# adapter_v1_2.net
KiCad netlist of a schematic drawn in EAGLE
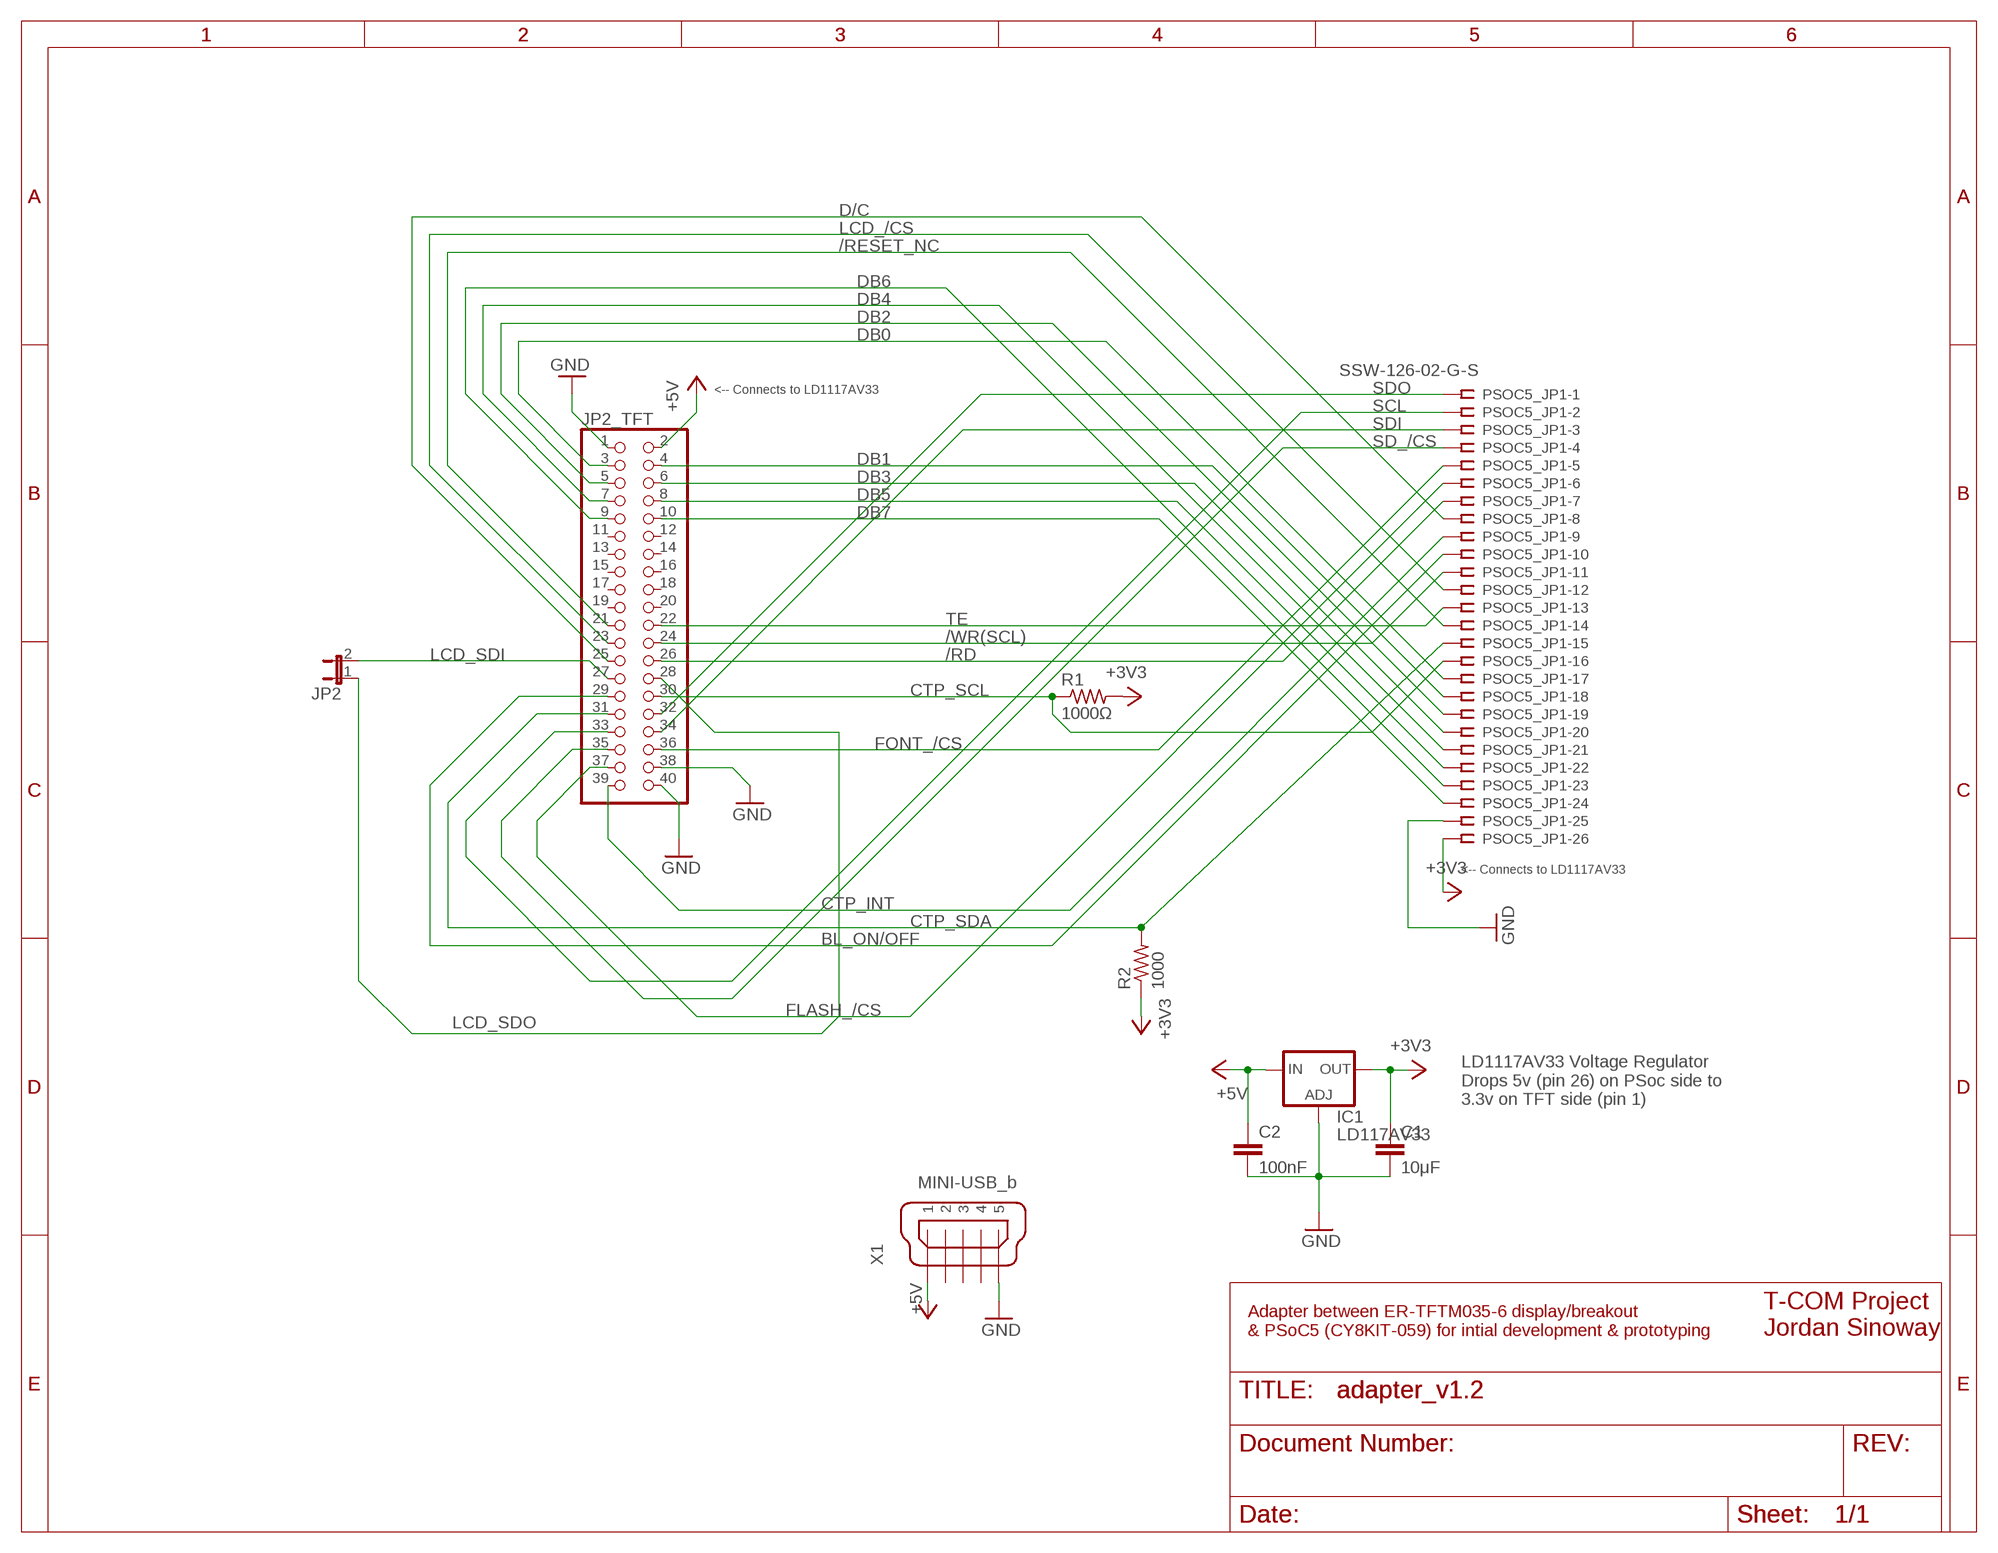
[diagram p0: schematic, sheet 1]

(export (version "E")
  (design (tool "Eeschema 10.0.6"))
  (components
    (comp (ref "C1")
      (value "10μF")
      (footprint "eagle-import:C2.5-2")
      (libsource (lib "eagle-import") (part "C2.5/2"))
    )
    (comp (ref "C2")
      (value "100nF")
      (footprint "eagle-import:C2.5-2")
      (libsource (lib "eagle-import") (part "C2.5/2"))
    )
    (comp (ref "IC1")
      (value "LD117AV33")
      (footprint "eagle-import:TO220L1")
      (libsource (lib "eagle-import") (part "LD117A?V33"))
    )
    (comp (ref "JP2")
      (value "JP1E")
      (footprint "eagle-import:JP1")
      (libsource (lib "eagle-import") (part "JP1E"))
    )
    (comp (ref "JP2_TFT")
      (value "PINHD-2X20")
      (footprint "eagle-import:2X20")
      (libsource (lib "eagle-import") (part "PINHD-2X20"))
    )
    (comp (ref "PSOC5_JP1")
      (value "SSW-126-02-G-S")
      (footprint "eagle-import:SSW-126-02-G-S")
      (fields (field (name "MF") "Samtec Inc."))
      (libsource (lib "eagle-import") (part "SSW-126-02-G-S"))
    )
    (comp (ref "R1")
      (value "1000Ω")
      (footprint "eagle-import:0204_7")
      (libsource (lib "eagle-import") (part "R-US_0204/7"))
    )
    (comp (ref "R2")
      (value "1000")
      (footprint "eagle-import:0204_7")
      (libsource (lib "eagle-import") (part "R-US_0204/7"))
    )
    (comp (ref "X1")
      (value "MINI-USB_b")
      (footprint "eagle-import:32005-601")
      (libsource (lib "eagle-import") (part "MINI-USB_SHIELD5P2-32005-601"))
    )
  )
  (nets
    (net (code "1") (name "+3V3") (class "Default")
      (node (ref "C1") (pin "1") (pinfunction "1_1") (pintype "passive"))
      (node (ref "IC1") (pin "2") (pinfunction "OUT_2") (pintype "passive"))
      (node (ref "PSOC5_JP1") (pin "26") (pinfunction "1_26") (pintype "passive"))
      (node (ref "R1") (pin "2") (pinfunction "2_2") (pintype "passive"))
      (node (ref "R2") (pin "1") (pinfunction "1_1") (pintype "passive"))
    )
    (net (code "2") (name "+5V") (class "Default")
      (node (ref "C2") (pin "1") (pinfunction "1_1") (pintype "passive"))
      (node (ref "IC1") (pin "3") (pinfunction "IN_3") (pintype "input"))
      (node (ref "JP2_TFT") (pin "2") (pinfunction "2_2") (pintype "passive"))
      (node (ref "X1") (pin "1") (pinfunction "1_1") (pintype "passive"))
    )
    (net (code "3") (name "/BL_ON{slash}OFF") (class "Default")
      (node (ref "JP2_TFT") (pin "29") (pinfunction "29_29") (pintype "passive"))
      (node (ref "PSOC5_JP1") (pin "10") (pinfunction "1_10") (pintype "passive"))
    )
    (net (code "4") (name "/CTP_INT") (class "Default")
      (node (ref "JP2_TFT") (pin "39") (pinfunction "39_39") (pintype "passive"))
      (node (ref "PSOC5_JP1") (pin "9") (pinfunction "1_9") (pintype "passive"))
    )
    (net (code "5") (name "/CTP_SCL") (class "Default")
      (node (ref "JP2_TFT") (pin "30") (pinfunction "30_30") (pintype "passive"))
      (node (ref "PSOC5_JP1") (pin "16") (pinfunction "1_16") (pintype "passive"))
      (node (ref "R1") (pin "1") (pinfunction "1_1") (pintype "passive"))
    )
    (net (code "6") (name "/CTP_SDA") (class "Default")
      (node (ref "JP2_TFT") (pin "31") (pinfunction "31_31") (pintype "passive"))
      (node (ref "PSOC5_JP1") (pin "15") (pinfunction "1_15") (pintype "passive"))
      (node (ref "R2") (pin "2") (pinfunction "2_2") (pintype "passive"))
    )
    (net (code "7") (name "/DB0") (class "Default")
      (node (ref "JP2_TFT") (pin "3") (pinfunction "3_3") (pintype "passive"))
      (node (ref "PSOC5_JP1") (pin "17") (pinfunction "1_17") (pintype "passive"))
    )
    (net (code "8") (name "/DB1") (class "Default")
      (node (ref "JP2_TFT") (pin "4") (pinfunction "4_4") (pintype "passive"))
      (node (ref "PSOC5_JP1") (pin "18") (pinfunction "1_18") (pintype "passive"))
    )
    (net (code "9") (name "/DB2") (class "Default")
      (node (ref "JP2_TFT") (pin "5") (pinfunction "5_5") (pintype "passive"))
      (node (ref "PSOC5_JP1") (pin "19") (pinfunction "1_19") (pintype "passive"))
    )
    (net (code "10") (name "/DB3") (class "Default")
      (node (ref "JP2_TFT") (pin "6") (pinfunction "6_6") (pintype "passive"))
      (node (ref "PSOC5_JP1") (pin "20") (pinfunction "1_20") (pintype "passive"))
    )
    (net (code "11") (name "/DB4") (class "Default")
      (node (ref "JP2_TFT") (pin "7") (pinfunction "7_7") (pintype "passive"))
      (node (ref "PSOC5_JP1") (pin "21") (pinfunction "1_21") (pintype "passive"))
    )
    (net (code "12") (name "/DB5") (class "Default")
      (node (ref "JP2_TFT") (pin "8") (pinfunction "8_8") (pintype "passive"))
      (node (ref "PSOC5_JP1") (pin "22") (pinfunction "1_22") (pintype "passive"))
    )
    (net (code "13") (name "/DB6") (class "Default")
      (node (ref "JP2_TFT") (pin "9") (pinfunction "9_9") (pintype "passive"))
      (node (ref "PSOC5_JP1") (pin "23") (pinfunction "1_23") (pintype "passive"))
    )
    (net (code "14") (name "/DB7") (class "Default")
      (node (ref "JP2_TFT") (pin "10") (pinfunction "10_10") (pintype "passive"))
      (node (ref "PSOC5_JP1") (pin "24") (pinfunction "1_24") (pintype "passive"))
    )
    (net (code "15") (name "/D{slash}C") (class "Default")
      (node (ref "JP2_TFT") (pin "25") (pinfunction "25_25") (pintype "passive"))
      (node (ref "PSOC5_JP1") (pin "8") (pinfunction "1_8") (pintype "passive"))
    )
    (net (code "16") (name "/FLASH_{slash}CS") (class "Default")
      (node (ref "JP2_TFT") (pin "37") (pinfunction "37_37") (pintype "passive"))
      (node (ref "PSOC5_JP1") (pin "6") (pinfunction "1_6") (pintype "passive"))
    )
    (net (code "17") (name "/FONT_{slash}CS") (class "Default")
      (node (ref "JP2_TFT") (pin "36") (pinfunction "36_36") (pintype "passive"))
      (node (ref "PSOC5_JP1") (pin "5") (pinfunction "1_5") (pintype "passive"))
    )
    (net (code "18") (name "/LCD_SDI") (class "Default")
      (node (ref "JP2") (pin "2") (pinfunction "2_2") (pintype "passive"))
      (node (ref "JP2_TFT") (pin "27") (pinfunction "27_27") (pintype "passive"))
    )
    (net (code "19") (name "/LCD_SDO") (class "Default")
      (node (ref "JP2") (pin "1") (pinfunction "1_1") (pintype "passive"))
      (node (ref "JP2_TFT") (pin "28") (pinfunction "28_28") (pintype "passive"))
    )
    (net (code "20") (name "/LCD_{slash}CS") (class "Default")
      (node (ref "JP2_TFT") (pin "23") (pinfunction "23_23") (pintype "passive"))
      (node (ref "PSOC5_JP1") (pin "12") (pinfunction "1_12") (pintype "passive"))
    )
    (net (code "21") (name "/SCL") (class "Default")
      (node (ref "JP2_TFT") (pin "33") (pinfunction "33_33") (pintype "passive"))
      (node (ref "PSOC5_JP1") (pin "2") (pinfunction "1_2") (pintype "passive"))
    )
    (net (code "22") (name "/SDI") (class "Default")
      (node (ref "JP2_TFT") (pin "34") (pinfunction "34_34") (pintype "passive"))
      (node (ref "PSOC5_JP1") (pin "3") (pinfunction "1_3") (pintype "passive"))
    )
    (net (code "23") (name "/SDO") (class "Default")
      (node (ref "JP2_TFT") (pin "32") (pinfunction "32_32") (pintype "passive"))
      (node (ref "PSOC5_JP1") (pin "1") (pinfunction "1_1") (pintype "passive"))
    )
    (net (code "24") (name "/SD_{slash}CS") (class "Default")
      (node (ref "JP2_TFT") (pin "35") (pinfunction "35_35") (pintype "passive"))
      (node (ref "PSOC5_JP1") (pin "4") (pinfunction "1_4") (pintype "passive"))
    )
    (net (code "25") (name "/TE") (class "Default")
      (node (ref "JP2_TFT") (pin "22") (pinfunction "22_22") (pintype "passive"))
      (node (ref "PSOC5_JP1") (pin "13") (pinfunction "1_13") (pintype "passive"))
    )
    (net (code "26") (name "/{slash}RD") (class "Default")
      (node (ref "JP2_TFT") (pin "26") (pinfunction "26_26") (pintype "passive"))
      (node (ref "PSOC5_JP1") (pin "7") (pinfunction "1_7") (pintype "passive"))
    )
    (net (code "27") (name "/{slash}RESET_NC") (class "Default")
      (node (ref "JP2_TFT") (pin "21") (pinfunction "21_21") (pintype "passive"))
      (node (ref "PSOC5_JP1") (pin "14") (pinfunction "1_14") (pintype "passive"))
    )
    (net (code "28") (name "/{slash}WR(SCL)") (class "Default")
      (node (ref "JP2_TFT") (pin "24") (pinfunction "24_24") (pintype "passive"))
      (node (ref "PSOC5_JP1") (pin "11") (pinfunction "1_11") (pintype "passive"))
    )
    (net (code "29") (name "GND") (class "Default")
      (node (ref "C1") (pin "2") (pinfunction "2_2") (pintype "passive"))
      (node (ref "C2") (pin "2") (pinfunction "2_2") (pintype "passive"))
      (node (ref "IC1") (pin "1") (pinfunction "ADJ_1") (pintype "input"))
      (node (ref "JP2_TFT") (pin "1") (pinfunction "1_1") (pintype "passive"))
      (node (ref "JP2_TFT") (pin "38") (pinfunction "38_38") (pintype "passive"))
      (node (ref "JP2_TFT") (pin "40") (pinfunction "40_40") (pintype "passive"))
      (node (ref "PSOC5_JP1") (pin "25") (pinfunction "1_25") (pintype "passive"))
      (node (ref "X1") (pin "5") (pinfunction "5_5") (pintype "passive"))
    )
    (net (code "30") (name "unconnected-(JP2_TFT-Pad11)") (class "Default")
      (node (ref "JP2_TFT") (pin "11") (pinfunction "11_11") (pintype "passive"))
    )
    (net (code "31") (name "unconnected-(JP2_TFT-Pad12)") (class "Default")
      (node (ref "JP2_TFT") (pin "12") (pinfunction "12_12") (pintype "passive"))
    )
    (net (code "32") (name "unconnected-(JP2_TFT-Pad13)") (class "Default")
      (node (ref "JP2_TFT") (pin "13") (pinfunction "13_13") (pintype "passive"))
    )
    (net (code "33") (name "unconnected-(JP2_TFT-Pad14)") (class "Default")
      (node (ref "JP2_TFT") (pin "14") (pinfunction "14_14") (pintype "passive"))
    )
    (net (code "34") (name "unconnected-(JP2_TFT-Pad15)") (class "Default")
      (node (ref "JP2_TFT") (pin "15") (pinfunction "15_15") (pintype "passive"))
    )
    (net (code "35") (name "unconnected-(JP2_TFT-Pad16)") (class "Default")
      (node (ref "JP2_TFT") (pin "16") (pinfunction "16_16") (pintype "passive"))
    )
    (net (code "36") (name "unconnected-(JP2_TFT-Pad17)") (class "Default")
      (node (ref "JP2_TFT") (pin "17") (pinfunction "17_17") (pintype "passive"))
    )
    (net (code "37") (name "unconnected-(JP2_TFT-Pad18)") (class "Default")
      (node (ref "JP2_TFT") (pin "18") (pinfunction "18_18") (pintype "passive"))
    )
    (net (code "38") (name "unconnected-(JP2_TFT-Pad19)") (class "Default")
      (node (ref "JP2_TFT") (pin "19") (pinfunction "19_19") (pintype "passive"))
    )
    (net (code "39") (name "unconnected-(JP2_TFT-Pad20)") (class "Default")
      (node (ref "JP2_TFT") (pin "20") (pinfunction "20_20") (pintype "passive"))
    )
    (net (code "40") (name "unconnected-(X1-Pad2)") (class "Default")
      (node (ref "X1") (pin "2") (pinfunction "2_2") (pintype "passive"))
    )
    (net (code "41") (name "unconnected-(X1-Pad3)") (class "Default")
      (node (ref "X1") (pin "3") (pinfunction "3_3") (pintype "passive"))
    )
    (net (code "42") (name "unconnected-(X1-Pad4)") (class "Default")
      (node (ref "X1") (pin "4") (pinfunction "4_4") (pintype "passive"))
    )
  )
)
